# lora-rpi-hat-fab4space.net
KiCad netlist of a schematic drawn in EAGLE
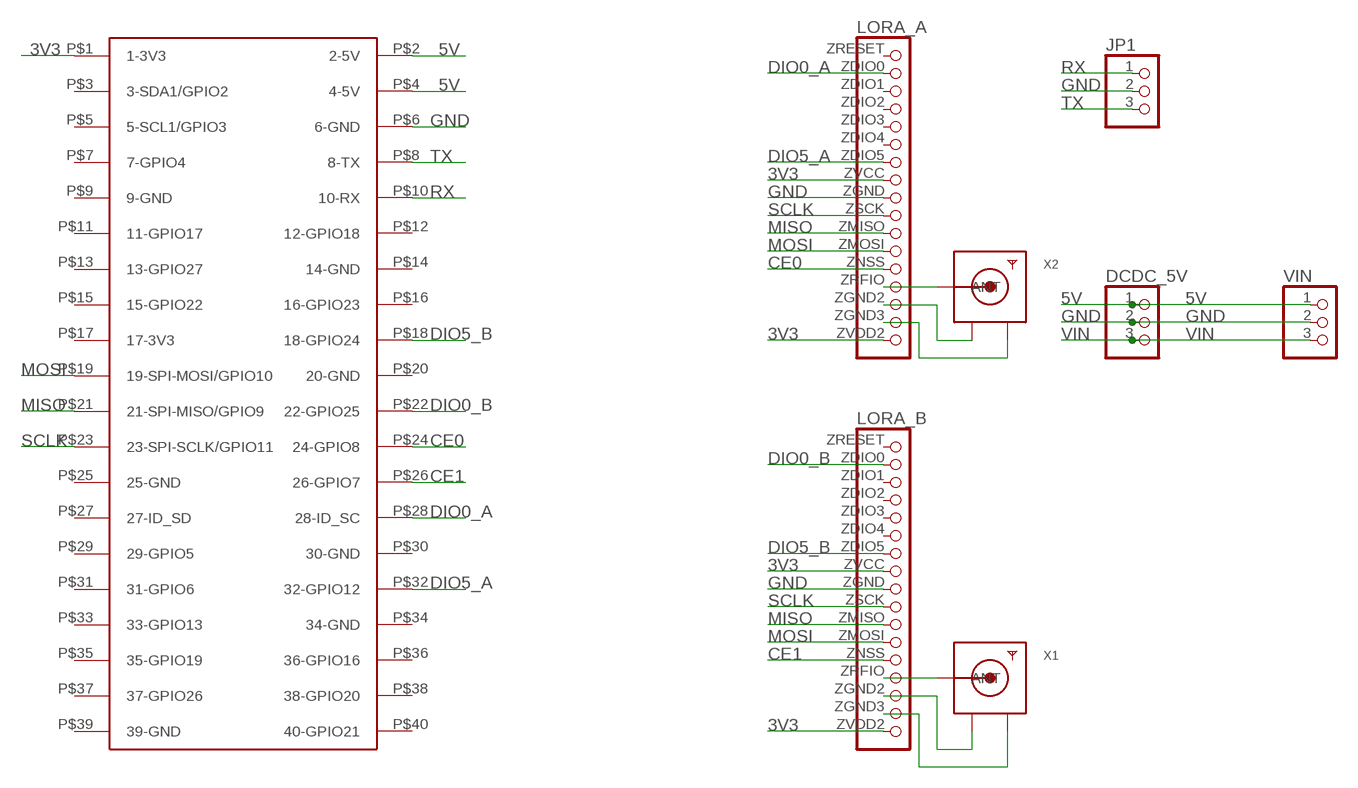
[diagram p0: schematic, sheet 1]

(export (version "E")
  (design (tool "Eeschema 10.0.6"))
  (components
    (comp (ref "DCDC_5V")
      (value "PINHD-1X3")
      (footprint "eagle-import:1X03")
      (libsource (lib "eagle-import") (part "PINHD-1X3"))
    )
    (comp (ref "JP1")
      (value "PINHD-1X3")
      (footprint "eagle-import:1X03")
      (libsource (lib "eagle-import") (part "PINHD-1X3"))
    )
    (comp (ref "LORA_A")
      (value "DRF1278F_BKOUTDP1276")
      (footprint "eagle-import:ANYLINK_DP1276")
      (libsource (lib "eagle-import") (part "DRF1278F_BKOUTDP1276"))
    )
    (comp (ref "LORA_B")
      (value "DRF1278F_BKOUTDP1276")
      (footprint "eagle-import:ANYLINK_DP1276")
      (libsource (lib "eagle-import") (part "DRF1278F_BKOUTDP1276"))
    )
    (comp (ref "U$1")
      (value "RASPBERRY-PI+")
      (footprint "eagle-import:RASPBERRY-PI-PLUS-CAM_NOTCH")
      (libsource (lib "eagle-import") (part "RASPBERRY-PI+"))
    )
    (comp (ref "VIN")
      (value "PINHD-1X3")
      (footprint "eagle-import:1X03")
      (libsource (lib "eagle-import") (part "PINHD-1X3"))
    )
    (comp (ref "X1")
      (value "SMACONNECTOR_EDGE")
      (footprint "eagle-import:SMA_EDGELAUNCH")
      (libsource (lib "eagle-import") (part "SMACONNECTOR_EDGE"))
    )
    (comp (ref "X2")
      (value "SMACONNECTOR_EDGE")
      (footprint "eagle-import:SMA_EDGELAUNCH")
      (libsource (lib "eagle-import") (part "SMACONNECTOR_EDGE"))
    )
  )
  (nets
    (net (code "1") (name "/3V3") (class "Default")
      (node (ref "LORA_A") (pin "ZVCC") (pinfunction "VCC_ZVCC") (pintype "passive"))
      (node (ref "LORA_A") (pin "ZVDD2") (pinfunction "VCC2_ZVDD2") (pintype "passive"))
      (node (ref "LORA_B") (pin "ZVCC") (pinfunction "VCC_ZVCC") (pintype "passive"))
      (node (ref "LORA_B") (pin "ZVDD2") (pinfunction "VCC2_ZVDD2") (pintype "passive"))
      (node (ref "U$1") (pin "P$1") (pinfunction "1-3V3_P$1") (pintype "bidirectional"))
    )
    (net (code "2") (name "/5V") (class "Default")
      (node (ref "DCDC_5V") (pin "1") (pinfunction "1_1") (pintype "passive"))
      (node (ref "U$1") (pin "P$2") (pinfunction "2-5V_P$2") (pintype "bidirectional"))
      (node (ref "U$1") (pin "P$4") (pinfunction "4-5V_P$4") (pintype "bidirectional"))
      (node (ref "VIN") (pin "1") (pinfunction "1_1") (pintype "passive"))
    )
    (net (code "3") (name "/CE0") (class "Default")
      (node (ref "LORA_A") (pin "ZNSS") (pinfunction "NSS_ZNSS") (pintype "passive"))
      (node (ref "U$1") (pin "P$24") (pinfunction "24-GPIO8_P$24") (pintype "bidirectional"))
    )
    (net (code "4") (name "/CE1") (class "Default")
      (node (ref "LORA_B") (pin "ZNSS") (pinfunction "NSS_ZNSS") (pintype "passive"))
      (node (ref "U$1") (pin "P$26") (pinfunction "26-GPIO7_P$26") (pintype "bidirectional"))
    )
    (net (code "5") (name "/DIO0_A") (class "Default")
      (node (ref "LORA_A") (pin "ZDIO0") (pinfunction "DIO0_ZDIO0") (pintype "passive"))
      (node (ref "U$1") (pin "P$28") (pinfunction "28-ID_SC_P$28") (pintype "bidirectional"))
    )
    (net (code "6") (name "/DIO0_B") (class "Default")
      (node (ref "LORA_B") (pin "ZDIO0") (pinfunction "DIO0_ZDIO0") (pintype "passive"))
      (node (ref "U$1") (pin "P$22") (pinfunction "22-GPIO25_P$22") (pintype "bidirectional"))
    )
    (net (code "7") (name "/DIO5_A") (class "Default")
      (node (ref "LORA_A") (pin "ZDIO5") (pinfunction "DIO5_ZDIO5") (pintype "passive"))
      (node (ref "U$1") (pin "P$32") (pinfunction "32-GPIO12_P$32") (pintype "bidirectional"))
    )
    (net (code "8") (name "/DIO5_B") (class "Default")
      (node (ref "LORA_B") (pin "ZDIO5") (pinfunction "DIO5_ZDIO5") (pintype "passive"))
      (node (ref "U$1") (pin "P$18") (pinfunction "18-GPIO24_P$18") (pintype "bidirectional"))
    )
    (net (code "9") (name "/GND") (class "Default")
      (node (ref "DCDC_5V") (pin "2") (pinfunction "2_2") (pintype "passive"))
      (node (ref "JP1") (pin "2") (pinfunction "2_2") (pintype "passive"))
      (node (ref "LORA_A") (pin "ZGND") (pinfunction "GND_ZGND") (pintype "passive"))
      (node (ref "LORA_B") (pin "ZGND") (pinfunction "GND_ZGND") (pintype "passive"))
      (node (ref "U$1") (pin "P$6") (pinfunction "6-GND_P$6") (pintype "bidirectional"))
      (node (ref "VIN") (pin "2") (pinfunction "2_2") (pintype "passive"))
    )
    (net (code "10") (name "/MISO") (class "Default")
      (node (ref "LORA_A") (pin "ZMISO") (pinfunction "MISO_ZMISO") (pintype "passive"))
      (node (ref "LORA_B") (pin "ZMISO") (pinfunction "MISO_ZMISO") (pintype "passive"))
      (node (ref "U$1") (pin "P$21") (pinfunction "21-SPI-MISO/GPIO9_P$21") (pintype "bidirectional"))
    )
    (net (code "11") (name "/MOSI") (class "Default")
      (node (ref "LORA_A") (pin "ZMOSI") (pinfunction "MOSI_ZMOSI") (pintype "passive"))
      (node (ref "LORA_B") (pin "ZMOSI") (pinfunction "MOSI_ZMOSI") (pintype "passive"))
      (node (ref "U$1") (pin "P$19") (pinfunction "19-SPI-MOSI/GPIO10_P$19") (pintype "bidirectional"))
    )
    (net (code "12") (name "/RX") (class "Default")
      (node (ref "JP1") (pin "1") (pinfunction "1_1") (pintype "passive"))
      (node (ref "U$1") (pin "P$10") (pinfunction "10-RX_P$10") (pintype "bidirectional"))
    )
    (net (code "13") (name "/SCLK") (class "Default")
      (node (ref "LORA_A") (pin "ZSCK") (pinfunction "SCK_ZSCK") (pintype "passive"))
      (node (ref "LORA_B") (pin "ZSCK") (pinfunction "SCK_ZSCK") (pintype "passive"))
      (node (ref "U$1") (pin "P$23") (pinfunction "23-SPI-SCLK/GPIO11_P$23") (pintype "bidirectional"))
    )
    (net (code "14") (name "/TX") (class "Default")
      (node (ref "JP1") (pin "3") (pinfunction "3_3") (pintype "passive"))
      (node (ref "U$1") (pin "P$8") (pinfunction "8-TX_P$8") (pintype "bidirectional"))
    )
    (net (code "15") (name "/VIN") (class "Default")
      (node (ref "DCDC_5V") (pin "3") (pinfunction "3_3") (pintype "passive"))
      (node (ref "VIN") (pin "3") (pinfunction "3_3") (pintype "passive"))
    )
    (net (code "16") (name "Net-(LORA_A-RFIO)") (class "Default")
      (node (ref "LORA_A") (pin "ZRFIO") (pinfunction "RFIO_ZRFIO") (pintype "passive"))
      (node (ref "X2") (pin "P") (pinfunction "ANT_P") (pintype "bidirectional"))
    )
    (net (code "17") (name "Net-(LORA_A-RGND1)") (class "Default")
      (node (ref "LORA_A") (pin "ZGND2") (pinfunction "RGND1_ZGND2") (pintype "passive"))
      (node (ref "X2") (pin "GND@2") (pinfunction "GND3_GND@2") (pintype "power_in"))
    )
    (net (code "18") (name "Net-(LORA_A-RGND2)") (class "Default")
      (node (ref "LORA_A") (pin "ZGND3") (pinfunction "RGND2_ZGND3") (pintype "passive"))
      (node (ref "X2") (pin "GND@1") (pinfunction "GND4_GND@1") (pintype "power_in"))
    )
    (net (code "19") (name "Net-(LORA_B-RFIO)") (class "Default")
      (node (ref "LORA_B") (pin "ZRFIO") (pinfunction "RFIO_ZRFIO") (pintype "passive"))
      (node (ref "X1") (pin "P") (pinfunction "ANT_P") (pintype "bidirectional"))
    )
    (net (code "20") (name "Net-(LORA_B-RGND1)") (class "Default")
      (node (ref "LORA_B") (pin "ZGND2") (pinfunction "RGND1_ZGND2") (pintype "passive"))
      (node (ref "X1") (pin "GND@2") (pinfunction "GND3_GND@2") (pintype "power_in"))
    )
    (net (code "21") (name "Net-(LORA_B-RGND2)") (class "Default")
      (node (ref "LORA_B") (pin "ZGND3") (pinfunction "RGND2_ZGND3") (pintype "passive"))
      (node (ref "X1") (pin "GND@1") (pinfunction "GND4_GND@1") (pintype "power_in"))
    )
    (net (code "22") (name "unconnected-(LORA_A-DIO1-PadZDIO1)") (class "Default")
      (node (ref "LORA_A") (pin "ZDIO1") (pinfunction "DIO1_ZDIO1") (pintype "passive"))
    )
    (net (code "23") (name "unconnected-(LORA_A-DIO2-PadZDIO2)") (class "Default")
      (node (ref "LORA_A") (pin "ZDIO2") (pinfunction "DIO2_ZDIO2") (pintype "passive"))
    )
    (net (code "24") (name "unconnected-(LORA_A-DIO3-PadZDIO3)") (class "Default")
      (node (ref "LORA_A") (pin "ZDIO3") (pinfunction "DIO3_ZDIO3") (pintype "passive"))
    )
    (net (code "25") (name "unconnected-(LORA_A-DIO4-PadZDIO4)") (class "Default")
      (node (ref "LORA_A") (pin "ZDIO4") (pinfunction "DIO4_ZDIO4") (pintype "passive"))
    )
    (net (code "26") (name "unconnected-(LORA_A-RESET-PadZRESET)") (class "Default")
      (node (ref "LORA_A") (pin "ZRESET") (pinfunction "RESET_ZRESET") (pintype "passive"))
    )
    (net (code "27") (name "unconnected-(LORA_B-DIO1-PadZDIO1)") (class "Default")
      (node (ref "LORA_B") (pin "ZDIO1") (pinfunction "DIO1_ZDIO1") (pintype "passive"))
    )
    (net (code "28") (name "unconnected-(LORA_B-DIO2-PadZDIO2)") (class "Default")
      (node (ref "LORA_B") (pin "ZDIO2") (pinfunction "DIO2_ZDIO2") (pintype "passive"))
    )
    (net (code "29") (name "unconnected-(LORA_B-DIO3-PadZDIO3)") (class "Default")
      (node (ref "LORA_B") (pin "ZDIO3") (pinfunction "DIO3_ZDIO3") (pintype "passive"))
    )
    (net (code "30") (name "unconnected-(LORA_B-DIO4-PadZDIO4)") (class "Default")
      (node (ref "LORA_B") (pin "ZDIO4") (pinfunction "DIO4_ZDIO4") (pintype "passive"))
    )
    (net (code "31") (name "unconnected-(LORA_B-RESET-PadZRESET)") (class "Default")
      (node (ref "LORA_B") (pin "ZRESET") (pinfunction "RESET_ZRESET") (pintype "passive"))
    )
    (net (code "32") (name "unconnected-(U$1-3-SDA1{slash}GPIO2-PadP$3)") (class "Default")
      (node (ref "U$1") (pin "P$3") (pinfunction "3-SDA1/GPIO2_P$3") (pintype "bidirectional"))
    )
    (net (code "33") (name "unconnected-(U$1-5-SCL1{slash}GPIO3-PadP$5)") (class "Default")
      (node (ref "U$1") (pin "P$5") (pinfunction "5-SCL1/GPIO3_P$5") (pintype "bidirectional"))
    )
    (net (code "34") (name "unconnected-(U$1-7-GPIO4-PadP$7)") (class "Default")
      (node (ref "U$1") (pin "P$7") (pinfunction "7-GPIO4_P$7") (pintype "bidirectional"))
    )
    (net (code "35") (name "unconnected-(U$1-9-GND-PadP$9)") (class "Default")
      (node (ref "U$1") (pin "P$9") (pinfunction "9-GND_P$9") (pintype "bidirectional"))
    )
    (net (code "36") (name "unconnected-(U$1-11-GPIO17-PadP$11)") (class "Default")
      (node (ref "U$1") (pin "P$11") (pinfunction "11-GPIO17_P$11") (pintype "bidirectional"))
    )
    (net (code "37") (name "unconnected-(U$1-12-GPIO18-PadP$12)") (class "Default")
      (node (ref "U$1") (pin "P$12") (pinfunction "12-GPIO18_P$12") (pintype "bidirectional"))
    )
    (net (code "38") (name "unconnected-(U$1-13-GPIO27-PadP$13)") (class "Default")
      (node (ref "U$1") (pin "P$13") (pinfunction "13-GPIO27_P$13") (pintype "bidirectional"))
    )
    (net (code "39") (name "unconnected-(U$1-14-GND-PadP$14)") (class "Default")
      (node (ref "U$1") (pin "P$14") (pinfunction "14-GND_P$14") (pintype "bidirectional"))
    )
    (net (code "40") (name "unconnected-(U$1-15-GPIO22-PadP$15)") (class "Default")
      (node (ref "U$1") (pin "P$15") (pinfunction "15-GPIO22_P$15") (pintype "bidirectional"))
    )
    (net (code "41") (name "unconnected-(U$1-16-GPIO23-PadP$16)") (class "Default")
      (node (ref "U$1") (pin "P$16") (pinfunction "16-GPIO23_P$16") (pintype "bidirectional"))
    )
    (net (code "42") (name "unconnected-(U$1-17-3V3-PadP$17)") (class "Default")
      (node (ref "U$1") (pin "P$17") (pinfunction "17-3V3_P$17") (pintype "bidirectional"))
    )
    (net (code "43") (name "unconnected-(U$1-20-GND-PadP$20)") (class "Default")
      (node (ref "U$1") (pin "P$20") (pinfunction "20-GND_P$20") (pintype "bidirectional"))
    )
    (net (code "44") (name "unconnected-(U$1-25-GND-PadP$25)") (class "Default")
      (node (ref "U$1") (pin "P$25") (pinfunction "25-GND_P$25") (pintype "bidirectional"))
    )
    (net (code "45") (name "unconnected-(U$1-27-ID_SD-PadP$27)") (class "Default")
      (node (ref "U$1") (pin "P$27") (pinfunction "27-ID_SD_P$27") (pintype "bidirectional"))
    )
    (net (code "46") (name "unconnected-(U$1-29-GPIO5-PadP$29)") (class "Default")
      (node (ref "U$1") (pin "P$29") (pinfunction "29-GPIO5_P$29") (pintype "bidirectional"))
    )
    (net (code "47") (name "unconnected-(U$1-30-GND-PadP$30)") (class "Default")
      (node (ref "U$1") (pin "P$30") (pinfunction "30-GND_P$30") (pintype "bidirectional"))
    )
    (net (code "48") (name "unconnected-(U$1-31-GPIO6-PadP$31)") (class "Default")
      (node (ref "U$1") (pin "P$31") (pinfunction "31-GPIO6_P$31") (pintype "bidirectional"))
    )
    (net (code "49") (name "unconnected-(U$1-33-GPIO13-PadP$33)") (class "Default")
      (node (ref "U$1") (pin "P$33") (pinfunction "33-GPIO13_P$33") (pintype "bidirectional"))
    )
    (net (code "50") (name "unconnected-(U$1-34-GND-PadP$34)") (class "Default")
      (node (ref "U$1") (pin "P$34") (pinfunction "34-GND_P$34") (pintype "bidirectional"))
    )
    (net (code "51") (name "unconnected-(U$1-35-GPIO19-PadP$35)") (class "Default")
      (node (ref "U$1") (pin "P$35") (pinfunction "35-GPIO19_P$35") (pintype "bidirectional"))
    )
    (net (code "52") (name "unconnected-(U$1-36-GPIO16-PadP$36)") (class "Default")
      (node (ref "U$1") (pin "P$36") (pinfunction "36-GPIO16_P$36") (pintype "bidirectional"))
    )
    (net (code "53") (name "unconnected-(U$1-37-GPIO26-PadP$37)") (class "Default")
      (node (ref "U$1") (pin "P$37") (pinfunction "37-GPIO26_P$37") (pintype "bidirectional"))
    )
    (net (code "54") (name "unconnected-(U$1-38-GPIO20-PadP$38)") (class "Default")
      (node (ref "U$1") (pin "P$38") (pinfunction "38-GPIO20_P$38") (pintype "bidirectional"))
    )
    (net (code "55") (name "unconnected-(U$1-39-GND-PadP$39)") (class "Default")
      (node (ref "U$1") (pin "P$39") (pinfunction "39-GND_P$39") (pintype "bidirectional"))
    )
    (net (code "56") (name "unconnected-(U$1-40-GPIO21-PadP$40)") (class "Default")
      (node (ref "U$1") (pin "P$40") (pinfunction "40-GPIO21_P$40") (pintype "bidirectional"))
    )
  )
)
